# EuroWizard.net
KiCad netlist of a schematic drawn in EAGLE
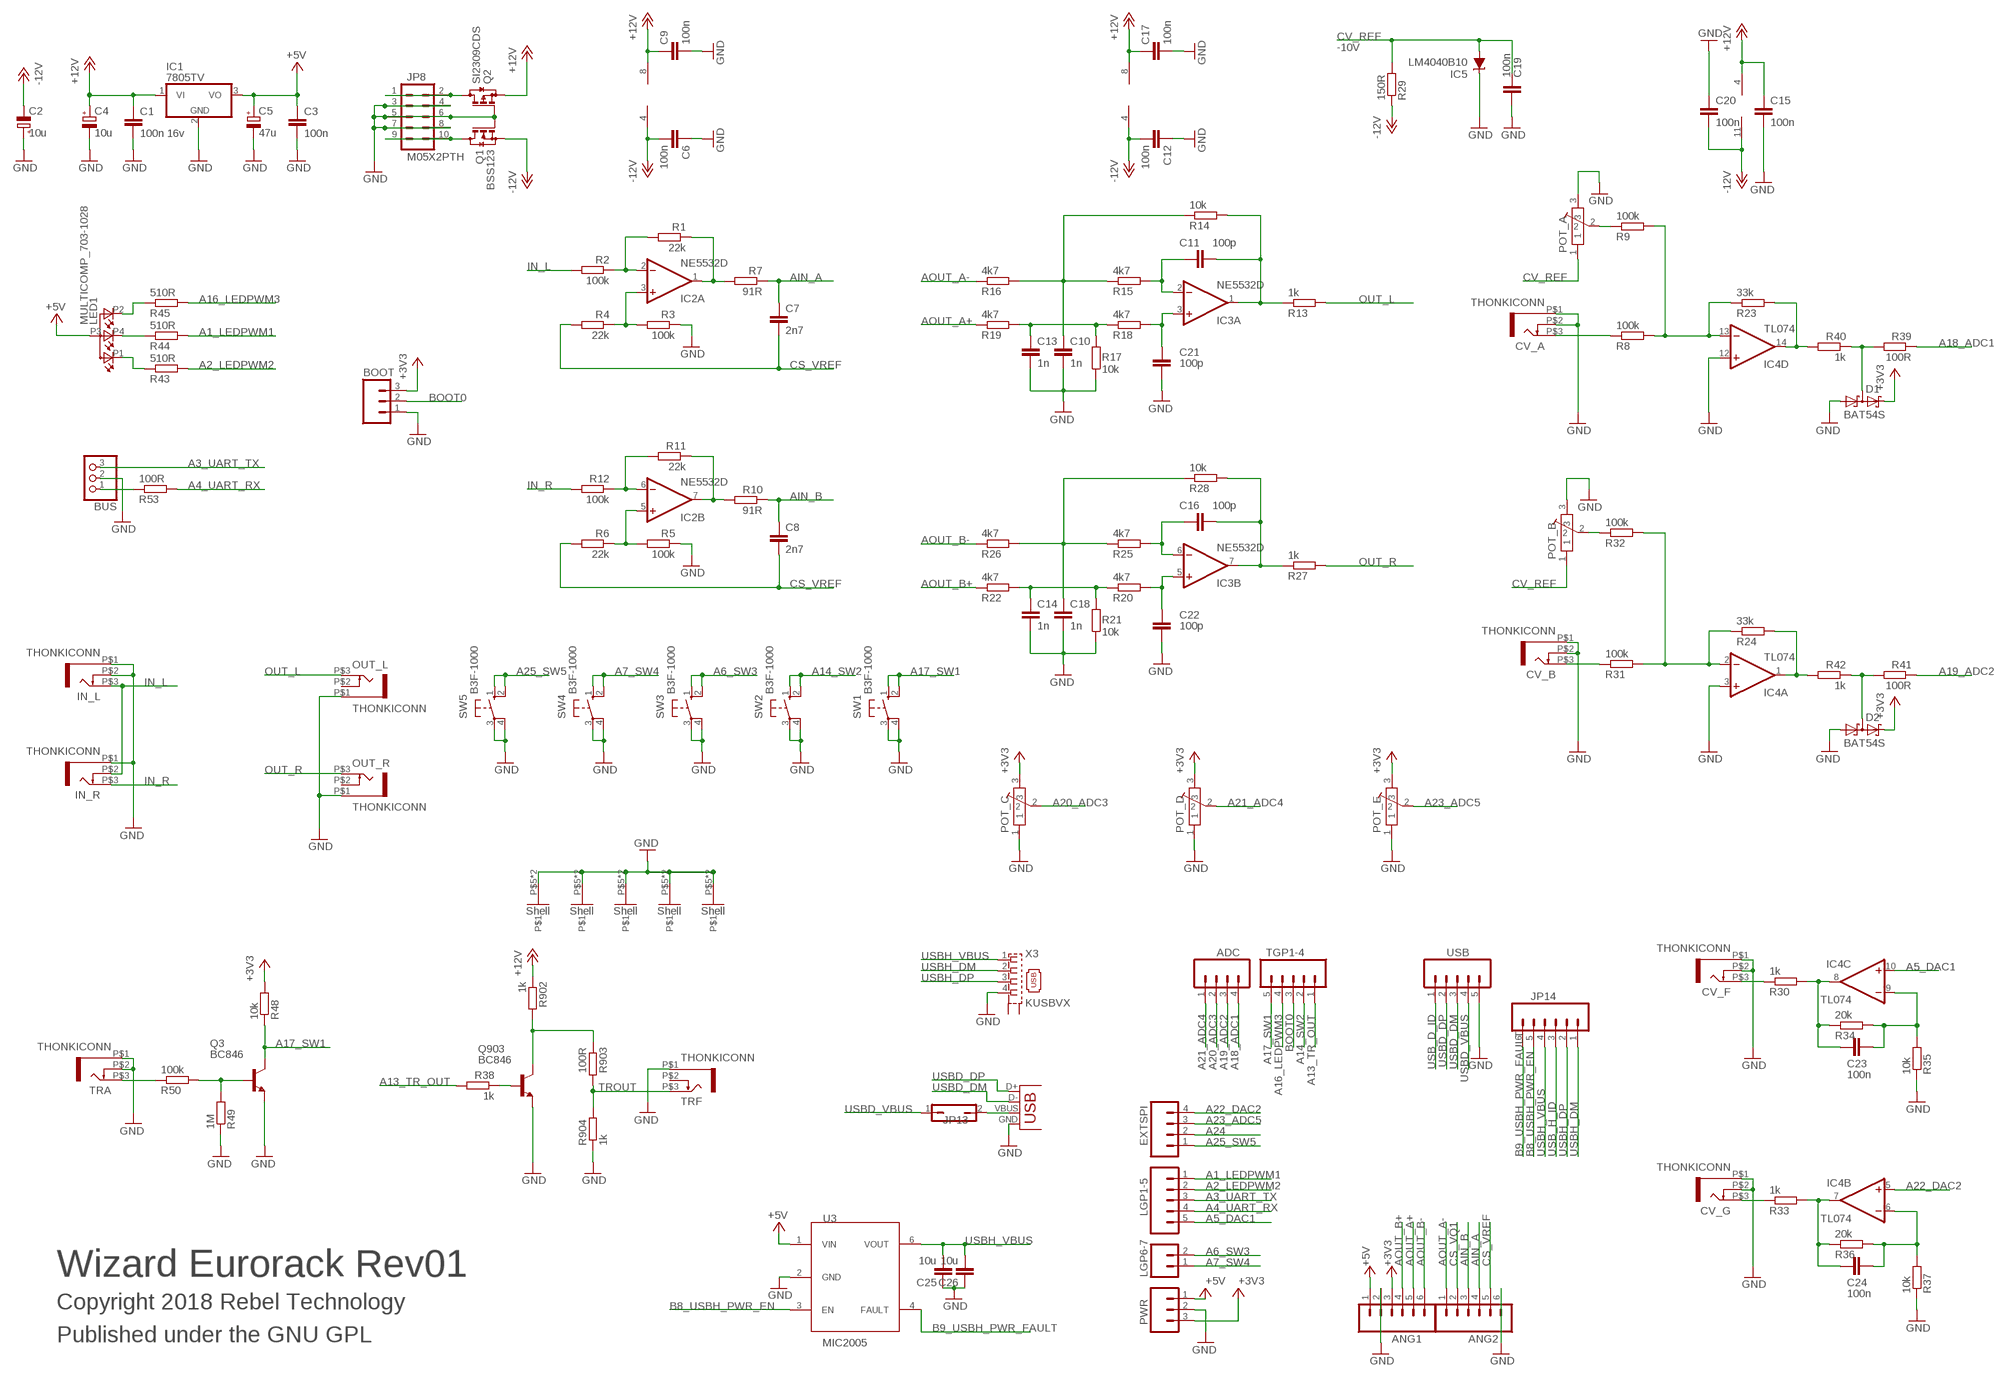
[diagram p0: schematic, sheet 1]

(export (version "E")
  (design (tool "Eeschema 10.0.6"))
  (components
    (comp (ref "ADC")
      (value "M04PTH")
      (footprint "eagle-import:1X04")
      (libsource (lib "eagle-import") (part "M04PTH"))
    )
    (comp (ref "ANG1")
      (value "M06SIP")
      (footprint "eagle-import:1X06")
      (libsource (lib "eagle-import") (part "M06SIP"))
    )
    (comp (ref "ANG2")
      (value "M06SIP")
      (footprint "eagle-import:1X06")
      (libsource (lib "eagle-import") (part "M06SIP"))
    )
    (comp (ref "BOOT")
      (value "M03PTH")
      (footprint "eagle-import:1X03")
      (libsource (lib "eagle-import") (part "M03PTH"))
    )
    (comp (ref "BUS")
      (value "CON-JST-1X03PH-TH")
      (footprint "eagle-import:JST-B3B-PH-KL")
      (libsource (lib "eagle-import") (part "CON-JST-1X03PH-TH"))
    )
    (comp (ref "C1")
      (value "100n 16v")
      (footprint "eagle-import:C0603")
      (libsource (lib "eagle-import") (part "C-EUC0603"))
    )
    (comp (ref "C2")
      (value "10u")
      (footprint "eagle-import:UD-4X5,8_NICHICON")
      (libsource (lib "eagle-import") (part "CPOL-EUUD-4X5,8"))
    )
    (comp (ref "C3")
      (value "100n")
      (footprint "eagle-import:C0603")
      (libsource (lib "eagle-import") (part "C-EUC0603"))
    )
    (comp (ref "C4")
      (value "10u")
      (footprint "eagle-import:UD-4X5,8_NICHICON")
      (libsource (lib "eagle-import") (part "CPOL-EUUD-4X5,8"))
    )
    (comp (ref "C5")
      (value "47u")
      (footprint "eagle-import:UD-4X5,8_NICHICON")
      (libsource (lib "eagle-import") (part "rcl_CPOL-EUUD-4X5,8"))
    )
    (comp (ref "C6")
      (value "100n")
      (footprint "eagle-import:C0603")
      (libsource (lib "eagle-import") (part "resistor_C-EUC0603"))
    )
    (comp (ref "C7")
      (value "2n7")
      (footprint "eagle-import:C0603")
      (libsource (lib "eagle-import") (part "resistor_C-EUC0603"))
    )
    (comp (ref "C8")
      (value "2n7")
      (footprint "eagle-import:C0603")
      (libsource (lib "eagle-import") (part "resistor_C-EUC0603"))
    )
    (comp (ref "C9")
      (value "100n")
      (footprint "eagle-import:C0603")
      (libsource (lib "eagle-import") (part "resistor_C-EUC0603"))
    )
    (comp (ref "C10")
      (value "1n")
      (footprint "eagle-import:C0603")
      (libsource (lib "eagle-import") (part "resistor_C-EUC0603"))
    )
    (comp (ref "C11")
      (value "100p")
      (footprint "eagle-import:C0603")
      (libsource (lib "eagle-import") (part "resistor_C-EUC0603"))
    )
    (comp (ref "C12")
      (value "100n")
      (footprint "eagle-import:C0603")
      (libsource (lib "eagle-import") (part "resistor_C-EUC0603"))
    )
    (comp (ref "C13")
      (value "1n")
      (footprint "eagle-import:C0603")
      (libsource (lib "eagle-import") (part "resistor_C-EUC0603"))
    )
    (comp (ref "C14")
      (value "1n")
      (footprint "eagle-import:C0603")
      (libsource (lib "eagle-import") (part "resistor_C-EUC0603"))
    )
    (comp (ref "C15")
      (value "100n")
      (footprint "eagle-import:C0603")
      (libsource (lib "eagle-import") (part "resistor_C-EUC0603"))
    )
    (comp (ref "C16")
      (value "100p")
      (footprint "eagle-import:C0603")
      (libsource (lib "eagle-import") (part "resistor_C-EUC0603"))
    )
    (comp (ref "C17")
      (value "100n")
      (footprint "eagle-import:C0603")
      (libsource (lib "eagle-import") (part "resistor_C-EUC0603"))
    )
    (comp (ref "C18")
      (value "1n")
      (footprint "eagle-import:C0603")
      (libsource (lib "eagle-import") (part "resistor_C-EUC0603"))
    )
    (comp (ref "C19")
      (value "100n")
      (footprint "eagle-import:C0603")
      (libsource (lib "eagle-import") (part "resistor_C-EUC0603"))
    )
    (comp (ref "C20")
      (value "100n")
      (footprint "eagle-import:C0603")
      (libsource (lib "eagle-import") (part "resistor_C-EUC0603"))
    )
    (comp (ref "C21")
      (value "100p")
      (footprint "eagle-import:C0603")
      (libsource (lib "eagle-import") (part "resistor_C-EUC0603"))
    )
    (comp (ref "C22")
      (value "100p")
      (footprint "eagle-import:C0603")
      (libsource (lib "eagle-import") (part "resistor_C-EUC0603"))
    )
    (comp (ref "C23")
      (value "100n")
      (footprint "eagle-import:C0603")
      (libsource (lib "eagle-import") (part "C-EUC0603"))
    )
    (comp (ref "C24")
      (value "100n")
      (footprint "eagle-import:C0603")
      (libsource (lib "eagle-import") (part "C-EUC0603"))
    )
    (comp (ref "C25")
      (value "10u")
      (footprint "eagle-import:C0603")
      (libsource (lib "eagle-import") (part "resistor_C-EUC0603"))
    )
    (comp (ref "C26")
      (value "10u")
      (footprint "eagle-import:C0603")
      (libsource (lib "eagle-import") (part "resistor_C-EUC0603"))
    )
    (comp (ref "CV_A")
      (value "THONKICONN")
      (footprint "eagle-import:THONKICONN")
      (libsource (lib "eagle-import") (part "THONKICONN"))
    )
    (comp (ref "CV_B")
      (value "THONKICONN")
      (footprint "eagle-import:THONKICONN")
      (libsource (lib "eagle-import") (part "THONKICONN"))
    )
    (comp (ref "CV_F")
      (value "THONKICONN")
      (footprint "eagle-import:THONKICONN")
      (libsource (lib "eagle-import") (part "THONKICONN"))
    )
    (comp (ref "CV_G")
      (value "THONKICONN")
      (footprint "eagle-import:THONKICONN")
      (libsource (lib "eagle-import") (part "THONKICONN"))
    )
    (comp (ref "D1")
      (value "BAT54S")
      (footprint "eagle-import:SOT23")
      (libsource (lib "eagle-import") (part "BAT54S"))
    )
    (comp (ref "D2")
      (value "BAT54S")
      (footprint "eagle-import:SOT23")
      (libsource (lib "eagle-import") (part "BAT54S"))
    )
    (comp (ref "EXTSPI")
      (value "M04PTH")
      (footprint "eagle-import:1X04")
      (libsource (lib "eagle-import") (part "M04PTH"))
    )
    (comp (ref "IC1")
      (value "7805TV")
      (footprint "eagle-import:TO220V")
      (libsource (lib "eagle-import") (part "78TV05"))
    )
    (comp (ref "IC2")
      (value "NE5532D")
      (footprint "eagle-import:SO08")
      (libsource (lib "eagle-import") (part "NE5532D"))
    )
    (comp (ref "IC3")
      (value "NE5532D")
      (footprint "eagle-import:SO08")
      (libsource (lib "eagle-import") (part "NE5532D"))
    )
    (comp (ref "IC4")
      (value "TL074")
      (footprint "eagle-import:SO14")
      (libsource (lib "eagle-import") (part "QUAD_OPAMPD"))
    )
    (comp (ref "IC5")
      (value "LM4040B10")
      (footprint "eagle-import:DBZ_R-PDSO-G3")
      (fields (field (name "MF") "TEXAS INSTRUMENT CONNECTORS") (field (name "MPN") "LM4041C12QDBZT"))
      (libsource (lib "eagle-import") (part "LM4041DBZC12"))
    )
    (comp (ref "IN_L")
      (value "THONKICONN")
      (footprint "eagle-import:THONKICONN")
      (libsource (lib "eagle-import") (part "THONKICONN"))
    )
    (comp (ref "IN_R")
      (value "THONKICONN")
      (footprint "eagle-import:THONKICONN")
      (libsource (lib "eagle-import") (part "THONKICONN"))
    )
    (comp (ref "JP8")
      (value "M05X2PTH")
      (footprint "eagle-import:AVR_ICSP")
      (libsource (lib "eagle-import") (part "M05X2PTH"))
    )
    (comp (ref "JP13")
      (value "JP1Q")
      (footprint "eagle-import:JP1")
      (libsource (lib "eagle-import") (part "JP1Q"))
    )
    (comp (ref "JP14")
      (value "M06SIP")
      (footprint "eagle-import:1X06")
      (libsource (lib "eagle-import") (part "M06SIP"))
    )
    (comp (ref "LED1")
      (value "MULTICOMP_703-1028")
      (footprint "eagle-import:RGB-LED-703-1028")
      (libsource (lib "eagle-import") (part "MULTICOMP_703-1028"))
    )
    (comp (ref "LGP1-5")
      (value "M05PTH")
      (footprint "eagle-import:1X05")
      (libsource (lib "eagle-import") (part "M05PTH"))
    )
    (comp (ref "LGP6-7")
      (value "M02PTH")
      (footprint "eagle-import:1X02")
      (libsource (lib "eagle-import") (part "M02PTH"))
    )
    (comp (ref "OUT_L")
      (value "THONKICONN")
      (footprint "eagle-import:THONKICONN")
      (libsource (lib "eagle-import") (part "THONKICONN"))
    )
    (comp (ref "OUT_R")
      (value "THONKICONN")
      (footprint "eagle-import:THONKICONN")
      (libsource (lib "eagle-import") (part "THONKICONN"))
    )
    (comp (ref "POT_A")
      (value "POT-ALPS-RK09L1140")
      (footprint "eagle-import:POT-ALPS-RK09L1140")
      (libsource (lib "eagle-import") (part "POT-ALPS-RK09L1140"))
    )
    (comp (ref "POT_B")
      (value "POT-ALPS-RK09L1140")
      (footprint "eagle-import:POT-ALPS-RK09L1140")
      (libsource (lib "eagle-import") (part "POT-ALPS-RK09L1140"))
    )
    (comp (ref "POT_C")
      (value "POT-ALPS-RK09L1140")
      (footprint "eagle-import:POT-ALPS-RK09L1140")
      (libsource (lib "eagle-import") (part "POT-ALPS-RK09L1140"))
    )
    (comp (ref "POT_D")
      (value "POT-ALPS-RK09L1140")
      (footprint "eagle-import:POT-ALPS-RK09L1140")
      (libsource (lib "eagle-import") (part "POT-ALPS-RK09L1140"))
    )
    (comp (ref "POT_E")
      (value "POT-ALPS-RK09L1140")
      (footprint "eagle-import:POT-ALPS-RK09L1140")
      (libsource (lib "eagle-import") (part "POT-ALPS-RK09L1140"))
    )
    (comp (ref "PWR")
      (value "M03PTH")
      (footprint "eagle-import:1X03")
      (libsource (lib "eagle-import") (part "M03PTH"))
    )
    (comp (ref "Q1")
      (value "BSS123")
      (footprint "eagle-import:SOT23")
      (libsource (lib "eagle-import") (part "BSS123"))
    )
    (comp (ref "Q2")
      (value "SI2309CDS")
      (footprint "eagle-import:SOT23")
      (libsource (lib "eagle-import") (part "BSS84"))
    )
    (comp (ref "Q3")
      (value "BC846")
      (footprint "eagle-import:SOT23")
      (libsource (lib "eagle-import") (part "BC846"))
    )
    (comp (ref "Q903")
      (value "BC846")
      (footprint "eagle-import:SOT23")
      (libsource (lib "eagle-import") (part "BC846"))
    )
    (comp (ref "R1")
      (value "22k")
      (footprint "eagle-import:0603")
      (libsource (lib "eagle-import") (part "R-EU_0603"))
    )
    (comp (ref "R2")
      (value "100k")
      (footprint "eagle-import:0603")
      (libsource (lib "eagle-import") (part "R-EU_0603"))
    )
    (comp (ref "R3")
      (value "100k")
      (footprint "eagle-import:0603")
      (libsource (lib "eagle-import") (part "R-EU_0603"))
    )
    (comp (ref "R4")
      (value "22k")
      (footprint "eagle-import:0603")
      (libsource (lib "eagle-import") (part "R-EU_0603"))
    )
    (comp (ref "R5")
      (value "100k")
      (footprint "eagle-import:0603")
      (libsource (lib "eagle-import") (part "R-EU_0603"))
    )
    (comp (ref "R6")
      (value "22k")
      (footprint "eagle-import:0603")
      (libsource (lib "eagle-import") (part "R-EU_0603"))
    )
    (comp (ref "R7")
      (value "91R")
      (footprint "eagle-import:0603")
      (libsource (lib "eagle-import") (part "R-EU_0603"))
    )
    (comp (ref "R8")
      (value "100k")
      (footprint "eagle-import:0603")
      (libsource (lib "eagle-import") (part "R-EU_0603"))
    )
    (comp (ref "R9")
      (value "100k")
      (footprint "eagle-import:0603")
      (libsource (lib "eagle-import") (part "R-EU_0603"))
    )
    (comp (ref "R10")
      (value "91R")
      (footprint "eagle-import:0603")
      (libsource (lib "eagle-import") (part "R-EU_0603"))
    )
    (comp (ref "R11")
      (value "22k")
      (footprint "eagle-import:0603")
      (libsource (lib "eagle-import") (part "R-EU_0603"))
    )
    (comp (ref "R12")
      (value "100k")
      (footprint "eagle-import:0603")
      (libsource (lib "eagle-import") (part "R-EU_0603"))
    )
    (comp (ref "R13")
      (value "1k")
      (footprint "eagle-import:0603")
      (libsource (lib "eagle-import") (part "R-EU_0603"))
    )
    (comp (ref "R14")
      (value "10k")
      (footprint "eagle-import:0603")
      (libsource (lib "eagle-import") (part "R-EU_0603"))
    )
    (comp (ref "R15")
      (value "4k7")
      (footprint "eagle-import:0603")
      (libsource (lib "eagle-import") (part "R-EU_0603"))
    )
    (comp (ref "R16")
      (value "4k7")
      (footprint "eagle-import:0603")
      (libsource (lib "eagle-import") (part "R-EU_0603"))
    )
    (comp (ref "R17")
      (value "10k")
      (footprint "eagle-import:0603")
      (libsource (lib "eagle-import") (part "R-EU_0603"))
    )
    (comp (ref "R18")
      (value "4k7")
      (footprint "eagle-import:0603")
      (libsource (lib "eagle-import") (part "R-EU_0603"))
    )
    (comp (ref "R19")
      (value "4k7")
      (footprint "eagle-import:0603")
      (libsource (lib "eagle-import") (part "R-EU_0603"))
    )
    (comp (ref "R20")
      (value "4k7")
      (footprint "eagle-import:0603")
      (libsource (lib "eagle-import") (part "R-EU_0603"))
    )
    (comp (ref "R21")
      (value "10k")
      (footprint "eagle-import:0603")
      (libsource (lib "eagle-import") (part "R-EU_0603"))
    )
    (comp (ref "R22")
      (value "4k7")
      (footprint "eagle-import:0603")
      (libsource (lib "eagle-import") (part "R-EU_0603"))
    )
    (comp (ref "R23")
      (value "33k")
      (footprint "eagle-import:0603")
      (libsource (lib "eagle-import") (part "R-EU_0603"))
    )
    (comp (ref "R24")
      (value "33k")
      (footprint "eagle-import:0603")
      (libsource (lib "eagle-import") (part "R-EU_0603"))
    )
    (comp (ref "R25")
      (value "4k7")
      (footprint "eagle-import:0603")
      (libsource (lib "eagle-import") (part "R-EU_0603"))
    )
    (comp (ref "R26")
      (value "4k7")
      (footprint "eagle-import:0603")
      (libsource (lib "eagle-import") (part "R-EU_0603"))
    )
    (comp (ref "R27")
      (value "1k")
      (footprint "eagle-import:0603")
      (libsource (lib "eagle-import") (part "R-EU_0603"))
    )
    (comp (ref "R28")
      (value "10k")
      (footprint "eagle-import:0603")
      (libsource (lib "eagle-import") (part "R-EU_0603"))
    )
    (comp (ref "R29")
      (value "150R")
      (footprint "eagle-import:0603")
      (libsource (lib "eagle-import") (part "R-EU_0603"))
    )
    (comp (ref "R30")
      (value "1k")
      (footprint "eagle-import:0603")
      (libsource (lib "eagle-import") (part "R-EU_0603"))
    )
    (comp (ref "R31")
      (value "100k")
      (footprint "eagle-import:0603")
      (libsource (lib "eagle-import") (part "R-EU_0603"))
    )
    (comp (ref "R32")
      (value "100k")
      (footprint "eagle-import:0603")
      (libsource (lib "eagle-import") (part "R-EU_0603"))
    )
    (comp (ref "R33")
      (value "1k")
      (footprint "eagle-import:0603")
      (libsource (lib "eagle-import") (part "R-EU_0603"))
    )
    (comp (ref "R34")
      (value "20k")
      (footprint "eagle-import:0603")
      (libsource (lib "eagle-import") (part "R-EU_0603"))
    )
    (comp (ref "R35")
      (value "10k")
      (footprint "eagle-import:0603")
      (libsource (lib "eagle-import") (part "R-EU_0603"))
    )
    (comp (ref "R36")
      (value "20k")
      (footprint "eagle-import:0603")
      (libsource (lib "eagle-import") (part "R-EU_0603"))
    )
    (comp (ref "R37")
      (value "10k")
      (footprint "eagle-import:0603")
      (libsource (lib "eagle-import") (part "R-EU_0603"))
    )
    (comp (ref "R38")
      (value "1k")
      (footprint "eagle-import:0603")
      (libsource (lib "eagle-import") (part "R-EU_0603"))
    )
    (comp (ref "R39")
      (value "100R")
      (footprint "eagle-import:0603")
      (libsource (lib "eagle-import") (part "R-EU_0603"))
    )
    (comp (ref "R40")
      (value "1k")
      (footprint "eagle-import:0603")
      (libsource (lib "eagle-import") (part "R-EU_0603"))
    )
    (comp (ref "R41")
      (value "100R")
      (footprint "eagle-import:0603")
      (libsource (lib "eagle-import") (part "R-EU_0603"))
    )
    (comp (ref "R42")
      (value "1k")
      (footprint "eagle-import:0603")
      (libsource (lib "eagle-import") (part "R-EU_0603"))
    )
    (comp (ref "R43")
      (value "510R")
      (footprint "eagle-import:0603")
      (libsource (lib "eagle-import") (part "R-EU_0603"))
    )
    (comp (ref "R44")
      (value "510R")
      (footprint "eagle-import:0603")
      (libsource (lib "eagle-import") (part "R-EU_0603"))
    )
    (comp (ref "R45")
      (value "510R")
      (footprint "eagle-import:0603")
      (libsource (lib "eagle-import") (part "R-EU_0603"))
    )
    (comp (ref "R48")
      (value "10k")
      (footprint "eagle-import:0603")
      (libsource (lib "eagle-import") (part "R-EU_0603"))
    )
    (comp (ref "R49")
      (value "1M")
      (footprint "eagle-import:0603")
      (libsource (lib "eagle-import") (part "R-EU_0603"))
    )
    (comp (ref "R50")
      (value "100k")
      (footprint "eagle-import:0603")
      (libsource (lib "eagle-import") (part "R-EU_0603"))
    )
    (comp (ref "R53")
      (value "100R")
      (footprint "eagle-import:0603")
      (libsource (lib "eagle-import") (part "R-EU_0603"))
    )
    (comp (ref "R902")
      (value "1k")
      (footprint "eagle-import:0603")
      (libsource (lib "eagle-import") (part "R-EU_0603"))
    )
    (comp (ref "R903")
      (value "100R")
      (footprint "eagle-import:0603")
      (libsource (lib "eagle-import") (part "R-EU_0603"))
    )
    (comp (ref "R904")
      (value "1k")
      (footprint "eagle-import:0603")
      (libsource (lib "eagle-import") (part "R-EU_0603"))
    )
    (comp (ref "SW1")
      (value "B3F-1000")
      (footprint "eagle-import:B3F-10XX")
      (libsource (lib "eagle-import") (part "10-XX"))
    )
    (comp (ref "SW2")
      (value "B3F-1000")
      (footprint "eagle-import:B3F-10XX")
      (libsource (lib "eagle-import") (part "10-XX"))
    )
    (comp (ref "SW3")
      (value "B3F-1000")
      (footprint "eagle-import:B3F-10XX")
      (libsource (lib "eagle-import") (part "10-XX"))
    )
    (comp (ref "SW4")
      (value "B3F-1000")
      (footprint "eagle-import:B3F-10XX")
      (libsource (lib "eagle-import") (part "10-XX"))
    )
    (comp (ref "SW5")
      (value "B3F-1000")
      (footprint "eagle-import:B3F-10XX")
      (libsource (lib "eagle-import") (part "10-XX"))
    )
    (comp (ref "TGP1-4")
      (value "M05PTH")
      (footprint "eagle-import:1X05")
      (libsource (lib "eagle-import") (part "M05PTH"))
    )
    (comp (ref "TRA")
      (value "THONKICONN")
      (footprint "eagle-import:THONKICONN")
      (libsource (lib "eagle-import") (part "THONKICONN"))
    )
    (comp (ref "TRF")
      (value "THONKICONN")
      (footprint "eagle-import:THONKICONN")
      (libsource (lib "eagle-import") (part "THONKICONN"))
    )
    (comp (ref "U3")
      (value "MIC2005")
      (footprint "eagle-import:SOT23-6")
      (libsource (lib "eagle-import") (part "MIC2005"))
    )
    (comp (ref "USB")
      (value "M05PTH")
      (footprint "eagle-import:1X05")
      (libsource (lib "eagle-import") (part "M05PTH"))
    )
    (comp (ref "X3")
      (value "KUSBVX")
      (footprint "eagle-import:KUSBVX")
      (libsource (lib "eagle-import") (part "KUSBVX"))
    )
    (comp (ref "X5")
      (value "USBPTH-VERTICAL")
      (footprint "eagle-import:USB-B-PTH-VERTICAL")
      (libsource (lib "eagle-import") (part "USBPTH-VERTICAL"))
    )
  )
  (nets
    (net (code "1") (name "+3V3") (class "Default")
      (node (ref "ANG1") (pin "3") (pinfunction "3_3") (pintype "passive"))
      (node (ref "BOOT") (pin "3") (pinfunction "3_3") (pintype "passive"))
      (node (ref "D1") (pin "2") (pinfunction "C2_2") (pintype "passive"))
      (node (ref "D2") (pin "2") (pinfunction "C2_2") (pintype "passive"))
      (node (ref "POT_C") (pin "3") (pinfunction "3_3") (pintype "bidirectional"))
      (node (ref "POT_D") (pin "3") (pinfunction "3_3") (pintype "bidirectional"))
      (node (ref "POT_E") (pin "3") (pinfunction "3_3") (pintype "bidirectional"))
      (node (ref "PWR") (pin "3") (pinfunction "3_3") (pintype "passive"))
      (node (ref "R48") (pin "2") (pinfunction "2_2") (pintype "passive"))
    )
    (net (code "2") (name "+5V") (class "Default")
      (node (ref "ANG1") (pin "1") (pinfunction "1_1") (pintype "passive"))
      (node (ref "C3") (pin "1") (pinfunction "1_1") (pintype "passive"))
      (node (ref "C5") (pin "+") (pinfunction "+_+") (pintype "passive"))
      (node (ref "IC1") (pin "3") (pinfunction "VO_3") (pintype "passive"))
      (node (ref "LED1") (pin "P3") (pinfunction "A_P3") (pintype "passive"))
      (node (ref "PWR") (pin "1") (pinfunction "1_1") (pintype "passive"))
      (node (ref "U3") (pin "1") (pinfunction "VIN_1") (pintype "power_in"))
    )
    (net (code "3") (name "+12V") (class "Default")
      (node (ref "C1") (pin "1") (pinfunction "1_1") (pintype "passive"))
      (node (ref "C15") (pin "1") (pinfunction "1_1") (pintype "passive"))
      (node (ref "C17") (pin "1") (pinfunction "1_1") (pintype "passive"))
      (node (ref "C4") (pin "+") (pinfunction "+_+") (pintype "passive"))
      (node (ref "C9") (pin "1") (pinfunction "1_1") (pintype "passive"))
      (node (ref "IC1") (pin "1") (pinfunction "VI_1") (pintype "input"))
      (node (ref "IC2") (pin "8") (pinfunction "V+_8") (pintype "power_in"))
      (node (ref "IC3") (pin "8") (pinfunction "V+_8") (pintype "power_in"))
      (node (ref "IC4") (pin "4") (pinfunction "V+_4") (pintype "power_in"))
      (node (ref "Q2") (pin "2") (pinfunction "S_2") (pintype "passive"))
      (node (ref "R902") (pin "1") (pinfunction "1_1") (pintype "passive"))
    )
    (net (code "4") (name "-12V") (class "Default")
      (node (ref "C12") (pin "2") (pinfunction "2_2") (pintype "passive"))
      (node (ref "C2") (pin "-") (pinfunction "-_-") (pintype "passive"))
      (node (ref "C20") (pin "2") (pinfunction "2_2") (pintype "passive"))
      (node (ref "C6") (pin "2") (pinfunction "2_2") (pintype "passive"))
      (node (ref "IC2") (pin "4") (pinfunction "V-_4") (pintype "power_in"))
      (node (ref "IC3") (pin "4") (pinfunction "V-_4") (pintype "power_in"))
      (node (ref "IC4") (pin "11") (pinfunction "V-_11") (pintype "power_in"))
      (node (ref "Q1") (pin "2") (pinfunction "S_2") (pintype "passive"))
      (node (ref "R29") (pin "1") (pinfunction "1_1") (pintype "passive"))
    )
    (net (code "5") (name "/A1_LEDPWM1") (class "Default")
      (node (ref "LGP1-5") (pin "1") (pinfunction "1_1") (pintype "passive"))
      (node (ref "R44") (pin "2") (pinfunction "2_2") (pintype "passive"))
    )
    (net (code "6") (name "/A2_LEDPWM2") (class "Default")
      (node (ref "LGP1-5") (pin "2") (pinfunction "2_2") (pintype "passive"))
      (node (ref "R43") (pin "2") (pinfunction "2_2") (pintype "passive"))
    )
    (net (code "7") (name "/A3_UART_TX") (class "Default")
      (node (ref "BUS") (pin "3") (pinfunction "3_3") (pintype "passive"))
      (node (ref "LGP1-5") (pin "3") (pinfunction "3_3") (pintype "passive"))
    )
    (net (code "8") (name "/A4_UART_RX") (class "Default")
      (node (ref "LGP1-5") (pin "4") (pinfunction "4_4") (pintype "passive"))
      (node (ref "R53") (pin "2") (pinfunction "2_2") (pintype "passive"))
    )
    (net (code "9") (name "/A5_DAC1") (class "Default")
      (node (ref "IC4") (pin "10") (pinfunction "+IN_10") (pintype "input"))
      (node (ref "LGP1-5") (pin "5") (pinfunction "5_5") (pintype "passive"))
    )
    (net (code "10") (name "/A6_SW3") (class "Default")
      (node (ref "LGP6-7") (pin "2") (pinfunction "2_2") (pintype "passive"))
      (node (ref "SW3") (pin "1") (pinfunction "S_1") (pintype "passive"))
      (node (ref "SW3") (pin "2") (pinfunction "S1_2") (pintype "passive"))
    )
    (net (code "11") (name "/A7_SW4") (class "Default")
      (node (ref "LGP6-7") (pin "1") (pinfunction "1_1") (pintype "passive"))
      (node (ref "SW4") (pin "1") (pinfunction "S_1") (pintype "passive"))
      (node (ref "SW4") (pin "2") (pinfunction "S1_2") (pintype "passive"))
    )
    (net (code "12") (name "/A13_TR_OUT") (class "Default")
      (node (ref "R38") (pin "2") (pinfunction "2_2") (pintype "passive"))
      (node (ref "TGP1-4") (pin "1") (pinfunction "1_1") (pintype "passive"))
    )
    (net (code "13") (name "/A14_SW2") (class "Default")
      (node (ref "SW2") (pin "1") (pinfunction "S_1") (pintype "passive"))
      (node (ref "SW2") (pin "2") (pinfunction "S1_2") (pintype "passive"))
      (node (ref "TGP1-4") (pin "2") (pinfunction "2_2") (pintype "passive"))
    )
    (net (code "14") (name "/A16_LEDPWM3") (class "Default")
      (node (ref "R45") (pin "2") (pinfunction "2_2") (pintype "passive"))
      (node (ref "TGP1-4") (pin "4") (pinfunction "4_4") (pintype "passive"))
    )
    (net (code "15") (name "/A17_SW1") (class "Default")
      (node (ref "Q3") (pin "3") (pinfunction "C_3") (pintype "passive"))
      (node (ref "R48") (pin "1") (pinfunction "1_1") (pintype "passive"))
      (node (ref "SW1") (pin "1") (pinfunction "S_1") (pintype "passive"))
      (node (ref "SW1") (pin "2") (pinfunction "S1_2") (pintype "passive"))
      (node (ref "TGP1-4") (pin "5") (pinfunction "5_5") (pintype "passive"))
    )
    (net (code "16") (name "/A18_ADC1") (class "Default")
      (node (ref "ADC") (pin "4") (pinfunction "4_4") (pintype "passive"))
      (node (ref "R39") (pin "1") (pinfunction "1_1") (pintype "passive"))
    )
    (net (code "17") (name "/A19_ADC2") (class "Default")
      (node (ref "ADC") (pin "3") (pinfunction "3_3") (pintype "passive"))
      (node (ref "R41") (pin "1") (pinfunction "1_1") (pintype "passive"))
    )
    (net (code "18") (name "/A20_ADC3") (class "Default")
      (node (ref "ADC") (pin "2") (pinfunction "2_2") (pintype "passive"))
      (node (ref "POT_C") (pin "2") (pinfunction "2_2") (pintype "bidirectional"))
    )
    (net (code "19") (name "/A21_ADC4") (class "Default")
      (node (ref "ADC") (pin "1") (pinfunction "1_1") (pintype "passive"))
      (node (ref "POT_D") (pin "2") (pinfunction "2_2") (pintype "bidirectional"))
    )
    (net (code "20") (name "/A22_DAC2") (class "Default")
      (node (ref "EXTSPI") (pin "4") (pinfunction "4_4") (pintype "passive"))
      (node (ref "IC4") (pin "5") (pinfunction "+IN_5") (pintype "input"))
    )
    (net (code "21") (name "/A23_ADC5") (class "Default")
      (node (ref "EXTSPI") (pin "3") (pinfunction "3_3") (pintype "passive"))
      (node (ref "POT_E") (pin "2") (pinfunction "2_2") (pintype "bidirectional"))
    )
    (net (code "22") (name "/A24") (class "Default")
      (node (ref "EXTSPI") (pin "2") (pinfunction "2_2") (pintype "passive"))
    )
    (net (code "23") (name "/A25_SW5") (class "Default")
      (node (ref "EXTSPI") (pin "1") (pinfunction "1_1") (pintype "passive"))
      (node (ref "SW5") (pin "1") (pinfunction "S_1") (pintype "passive"))
      (node (ref "SW5") (pin "2") (pinfunction "S1_2") (pintype "passive"))
    )
    (net (code "24") (name "/AIN_A") (class "Default")
      (node (ref "ANG2") (pin "4") (pinfunction "4_4") (pintype "passive"))
      (node (ref "C7") (pin "1") (pinfunction "1_1") (pintype "passive"))
      (node (ref "R7") (pin "1") (pinfunction "1_1") (pintype "passive"))
    )
    (net (code "25") (name "/AIN_B") (class "Default")
      (node (ref "ANG2") (pin "3") (pinfunction "3_3") (pintype "passive"))
      (node (ref "C8") (pin "1") (pinfunction "1_1") (pintype "passive"))
      (node (ref "R10") (pin "1") (pinfunction "1_1") (pintype "passive"))
    )
    (net (code "26") (name "/AOUT_A+") (class "Default")
      (node (ref "ANG1") (pin "5") (pinfunction "5_5") (pintype "passive"))
      (node (ref "R19") (pin "1") (pinfunction "1_1") (pintype "passive"))
    )
    (net (code "27") (name "/AOUT_A-") (class "Default")
      (node (ref "ANG2") (pin "1") (pinfunction "1_1") (pintype "passive"))
      (node (ref "R16") (pin "1") (pinfunction "1_1") (pintype "passive"))
    )
    (net (code "28") (name "/AOUT_B+") (class "Default")
      (node (ref "ANG1") (pin "4") (pinfunction "4_4") (pintype "passive"))
      (node (ref "R22") (pin "1") (pinfunction "1_1") (pintype "passive"))
    )
    (net (code "29") (name "/AOUT_B-") (class "Default")
      (node (ref "ANG1") (pin "6") (pinfunction "6_6") (pintype "passive"))
      (node (ref "R26") (pin "1") (pinfunction "1_1") (pintype "passive"))
    )
    (net (code "30") (name "/B8_USBH_PWR_EN") (class "Default")
      (node (ref "JP14") (pin "5") (pinfunction "5_5") (pintype "passive"))
      (node (ref "U3") (pin "3") (pinfunction "EN_3") (pintype "input"))
    )
    (net (code "31") (name "/B9_USBH_PWR_FAULT") (class "Default")
      (node (ref "JP14") (pin "6") (pinfunction "6_6") (pintype "passive"))
      (node (ref "U3") (pin "4") (pinfunction "FAULT_4") (pintype "output"))
    )
    (net (code "32") (name "/BOOT0") (class "Default")
      (node (ref "BOOT") (pin "2") (pinfunction "2_2") (pintype "passive"))
      (node (ref "TGP1-4") (pin "3") (pinfunction "3_3") (pintype "passive"))
    )
    (net (code "33") (name "/CS_VQ1") (class "Default")
      (node (ref "ANG2") (pin "2") (pinfunction "2_2") (pintype "passive"))
    )
    (net (code "34") (name "/CS_VREF") (class "Default")
      (node (ref "ANG2") (pin "5") (pinfunction "5_5") (pintype "passive"))
      (node (ref "C7") (pin "2") (pinfunction "2_2") (pintype "passive"))
      (node (ref "C8") (pin "2") (pinfunction "2_2") (pintype "passive"))
      (node (ref "R4") (pin "2") (pinfunction "2_2") (pintype "passive"))
      (node (ref "R6") (pin "2") (pinfunction "2_2") (pintype "passive"))
    )
    (net (code "35") (name "/CV_REF") (class "Default")
      (node (ref "C19") (pin "1") (pinfunction "1_1") (pintype "passive"))
      (node (ref "IC5") (pin "2") (pinfunction "A_2") (pintype "passive"))
      (node (ref "POT_A") (pin "1") (pinfunction "1_1") (pintype "bidirectional"))
      (node (ref "POT_B") (pin "1") (pinfunction "1_1") (pintype "bidirectional"))
      (node (ref "R29") (pin "2") (pinfunction "2_2") (pintype "passive"))
    )
    (net (code "36") (name "/IN_L") (class "Default")
      (node (ref "IN_L") (pin "P$3") (pinfunction "3_P$3") (pintype "passive"))
      (node (ref "IN_R") (pin "P$2") (pinfunction "4_P$2") (pintype "passive"))
      (node (ref "R2") (pin "2") (pinfunction "2_2") (pintype "passive"))
    )
    (net (code "37") (name "/IN_R") (class "Default")
      (node (ref "IN_R") (pin "P$3") (pinfunction "3_P$3") (pintype "passive"))
      (node (ref "R12") (pin "2") (pinfunction "2_2") (pintype "passive"))
    )
    (net (code "38") (name "/OUT_L") (class "Default")
      (node (ref "OUT_L") (pin "P$3") (pinfunction "3_P$3") (pintype "passive"))
      (node (ref "R13") (pin "2") (pinfunction "2_2") (pintype "passive"))
    )
    (net (code "39") (name "/OUT_R") (class "Default")
      (node (ref "OUT_R") (pin "P$3") (pinfunction "3_P$3") (pintype "passive"))
      (node (ref "R27") (pin "2") (pinfunction "2_2") (pintype "passive"))
    )
    (net (code "40") (name "/TROUT") (class "Default")
      (node (ref "R903") (pin "2") (pinfunction "2_2") (pintype "passive"))
      (node (ref "R904") (pin "2") (pinfunction "2_2") (pintype "passive"))
      (node (ref "TRF") (pin "P$3") (pinfunction "3_P$3") (pintype "passive"))
    )
    (net (code "41") (name "/USBD_DM") (class "Default")
      (node (ref "USB") (pin "3") (pinfunction "3_3") (pintype "passive"))
      (node (ref "X5") (pin "D-") (pinfunction "D-_D-") (pintype "bidirectional"))
    )
    (net (code "42") (name "/USBD_DP") (class "Default")
      (node (ref "USB") (pin "2") (pinfunction "2_2") (pintype "passive"))
      (node (ref "X5") (pin "D+") (pinfunction "D+_D+") (pintype "bidirectional"))
    )
    (net (code "43") (name "/USBD_VBUS") (class "Default")
      (node (ref "JP13") (pin "1") (pinfunction "1_1") (pintype "passive"))
      (node (ref "USB") (pin "4") (pinfunction "4_4") (pintype "passive"))
    )
    (net (code "44") (name "/USBH_DM") (class "Default")
      (node (ref "JP14") (pin "1") (pinfunction "1_1") (pintype "passive"))
      (node (ref "X3") (pin "2") (pinfunction "2_2") (pintype "passive"))
    )
    (net (code "45") (name "/USBH_DP") (class "Default")
      (node (ref "JP14") (pin "2") (pinfunction "2_2") (pintype "passive"))
      (node (ref "X3") (pin "3") (pinfunction "3_3") (pintype "passive"))
    )
    (net (code "46") (name "/USBH_VBUS") (class "Default")
      (node (ref "C25") (pin "2") (pinfunction "2_2") (pintype "passive"))
      (node (ref "C26") (pin "2") (pinfunction "2_2") (pintype "passive"))
      (node (ref "JP14") (pin "4") (pinfunction "4_4") (pintype "passive"))
      (node (ref "U3") (pin "6") (pinfunction "VOUT_6") (pintype "output"))
      (node (ref "X3") (pin "1") (pinfunction "1_1") (pintype "passive"))
    )
    (net (code "47") (name "/USB_D_ID") (class "Default")
      (node (ref "USB") (pin "1") (pinfunction "1_1") (pintype "passive"))
    )
    (net (code "48") (name "/USB_H_ID") (class "Default")
      (node (ref "JP14") (pin "3") (pinfunction "3_3") (pintype "passive"))
    )
    (net (code "49") (name "GND") (class "Default")
      (node (ref "ANG1") (pin "2") (pinfunction "2_2") (pintype "passive"))
      (node (ref "ANG2") (pin "6") (pinfunction "6_6") (pintype "passive"))
      (node (ref "BOOT") (pin "1") (pinfunction "1_1") (pintype "passive"))
      (node (ref "BUS") (pin "2") (pinfunction "2_2") (pintype "passive"))
      (node (ref "C1") (pin "2") (pinfunction "2_2") (pintype "passive"))
      (node (ref "C10") (pin "2") (pinfunction "2_2") (pintype "passive"))
      (node (ref "C12") (pin "1") (pinfunction "1_1") (pintype "passive"))
      (node (ref "C13") (pin "2") (pinfunction "2_2") (pintype "passive"))
      (node (ref "C14") (pin "2") (pinfunction "2_2") (pintype "passive"))
      (node (ref "C15") (pin "2") (pinfunction "2_2") (pintype "passive"))
      (node (ref "C17") (pin "2") (pinfunction "2_2") (pintype "passive"))
      (node (ref "C18") (pin "2") (pinfunction "2_2") (pintype "passive"))
      (node (ref "C19") (pin "2") (pinfunction "2_2") (pintype "passive"))
      (node (ref "C2") (pin "+") (pinfunction "+_+") (pintype "passive"))
      (node (ref "C20") (pin "1") (pinfunction "1_1") (pintype "passive"))
      (node (ref "C21") (pin "2") (pinfunction "2_2") (pintype "passive"))
      (node (ref "C22") (pin "2") (pinfunction "2_2") (pintype "passive"))
      (node (ref "C25") (pin "1") (pinfunction "1_1") (pintype "passive"))
      (node (ref "C26") (pin "1") (pinfunction "1_1") (pintype "passive"))
      (node (ref "C3") (pin "2") (pinfunction "2_2") (pintype "passive"))
      (node (ref "C4") (pin "-") (pinfunction "-_-") (pintype "passive"))
      (node (ref "C5") (pin "-") (pinfunction "-_-") (pintype "passive"))
      (node (ref "C6") (pin "1") (pinfunction "1_1") (pintype "passive"))
      (node (ref "C9") (pin "2") (pinfunction "2_2") (pintype "passive"))
      (node (ref "CV_A") (pin "P$1") (pinfunction "5_P$1") (pintype "passive"))
      (node (ref "CV_A") (pin "P$2") (pinfunction "4_P$2") (pintype "passive"))
      (node (ref "CV_B") (pin "P$1") (pinfunction "5_P$1") (pintype "passive"))
      (node (ref "CV_B") (pin "P$2") (pinfunction "4_P$2") (pintype "passive"))
      (node (ref "CV_F") (pin "P$1") (pinfunction "5_P$1") (pintype "passive"))
      (node (ref "CV_F") (pin "P$2") (pinfunction "4_P$2") (pintype "passive"))
      (node (ref "CV_G") (pin "P$1") (pinfunction "5_P$1") (pintype "passive"))
      (node (ref "CV_G") (pin "P$2") (pinfunction "4_P$2") (pintype "passive"))
      (node (ref "D1") (pin "1") (pinfunction "A1_1") (pintype "passive"))
      (node (ref "D2") (pin "1") (pinfunction "A1_1") (pintype "passive"))
      (node (ref "IC1") (pin "2") (pinfunction "GND_2") (pintype "passive"))
      (node (ref "IC4") (pin "12") (pinfunction "+IN_12") (pintype "input"))
      (node (ref "IC4") (pin "3") (pinfunction "+IN_3") (pintype "input"))
      (node (ref "IC5") (pin "1") (pinfunction "C_1") (pintype "passive"))
      (node (ref "IN_L") (pin "P$1") (pinfunction "5_P$1") (pintype "passive"))
      (node (ref "IN_L") (pin "P$2") (pinfunction "4_P$2") (pintype "passive"))
      (node (ref "IN_R") (pin "P$1") (pinfunction "5_P$1") (pintype "passive"))
      (node (ref "JP8") (pin "3") (pinfunction "3_3") (pintype "passive"))
      (node (ref "JP8") (pin "4") (pinfunction "4_4") (pintype "passive"))
      (node (ref "JP8") (pin "5") (pinfunction "5_5") (pintype "passive"))
      (node (ref "JP8") (pin "6") (pinfunction "6_6") (pintype "passive"))
      (node (ref "JP8") (pin "7") (pinfunction "7_7") (pintype "passive"))
      (node (ref "JP8") (pin "8") (pinfunction "8_8") (pintype "passive"))
      (node (ref "OUT_L") (pin "P$1") (pinfunction "5_P$1") (pintype "passive"))
      (node (ref "OUT_R") (pin "P$1") (pinfunction "5_P$1") (pintype "passive"))
      (node (ref "POT_A") (pin "3") (pinfunction "3_3") (pintype "bidirectional"))
      (node (ref "POT_A") (pin "P$5") (pinfunction "P$1_P$5") (pintype "bidirectional"))
      (node (ref "POT_A") (pin "P$6") (pinfunction "P$1_P$6") (pintype "bidirectional"))
      (node (ref "POT_B") (pin "3") (pinfunction "3_3") (pintype "bidirectional"))
      (node (ref "POT_B") (pin "P$5") (pinfunction "P$1_P$5") (pintype "bidirectional"))
      (node (ref "POT_B") (pin "P$6") (pinfunction "P$1_P$6") (pintype "bidirectional"))
      (node (ref "POT_C") (pin "1") (pinfunction "1_1") (pintype "bidirectional"))
      (node (ref "POT_C") (pin "P$5") (pinfunction "P$1_P$5") (pintype "bidirectional"))
      (node (ref "POT_C") (pin "P$6") (pinfunction "P$1_P$6") (pintype "bidirectional"))
      (node (ref "POT_D") (pin "1") (pinfunction "1_1") (pintype "bidirectional"))
      (node (ref "POT_D") (pin "P$5") (pinfunction "P$1_P$5") (pintype "bidirectional"))
      (node (ref "POT_D") (pin "P$6") (pinfunction "P$1_P$6") (pintype "bidirectional"))
      (node (ref "POT_E") (pin "1") (pinfunction "1_1") (pintype "bidirectional"))
      (node (ref "POT_E") (pin "P$5") (pinfunction "P$1_P$5") (pintype "bidirectional"))
      (node (ref "POT_E") (pin "P$6") (pinfunction "P$1_P$6") (pintype "bidirectional"))
      (node (ref "PWR") (pin "2") (pinfunction "2_2") (pintype "passive"))
      (node (ref "Q1") (pin "1") (pinfunction "G_1") (pintype "passive"))
      (node (ref "Q2") (pin "1") (pinfunction "G_1") (pintype "passive"))
      (node (ref "Q3") (pin "2") (pinfunction "E_2") (pintype "passive"))
      (node (ref "Q903") (pin "2") (pinfunction "E_2") (pintype "passive"))
      (node (ref "R17") (pin "1") (pinfunction "1_1") (pintype "passive"))
      (node (ref "R21") (pin "1") (pinfunction "1_1") (pintype "passive"))
      (node (ref "R3") (pin "1") (pinfunction "1_1") (pintype "passive"))
      (node (ref "R35") (pin "1") (pinfunction "1_1") (pintype "passive"))
      (node (ref "R37") (pin "1") (pinfunction "1_1") (pintype "passive"))
      (node (ref "R49") (pin "1") (pinfunction "1_1") (pintype "passive"))
      (node (ref "R5") (pin "1") (pinfunction "1_1") (pintype "passive"))
      (node (ref "R904") (pin "1") (pinfunction "1_1") (pintype "passive"))
      (node (ref "SW1") (pin "3") (pinfunction "P_3") (pintype "passive"))
      (node (ref "SW1") (pin "4") (pinfunction "P1_4") (pintype "passive"))
      (node (ref "SW2") (pin "3") (pinfunction "P_3") (pintype "passive"))
      (node (ref "SW2") (pin "4") (pinfunction "P1_4") (pintype "passive"))
      (node (ref "SW3") (pin "3") (pinfunction "P_3") (pintype "passive"))
      (node (ref "SW3") (pin "4") (pinfunction "P1_4") (pintype "passive"))
      (node (ref "SW4") (pin "3") (pinfunction "P_3") (pintype "passive"))
      (node (ref "SW4") (pin "4") (pinfunction "P1_4") (pintype "passive"))
      (node (ref "SW5") (pin "3") (pinfunction "P_3") (pintype "passive"))
      (node (ref "SW5") (pin "4") (pinfunction "P1_4") (pintype "passive"))
      (node (ref "TRA") (pin "P$1") (pinfunction "5_P$1") (pintype "passive"))
      (node (ref "TRA") (pin "P$2") (pinfunction "4_P$2") (pintype "passive"))
      (node (ref "TRF") (pin "P$1") (pinfunction "5_P$1") (pintype "passive"))
      (node (ref "U3") (pin "2") (pinfunction "GND_2") (pintype "power_in"))
      (node (ref "USB") (pin "5") (pinfunction "5_5") (pintype "passive"))
      (node (ref "X3") (pin "4") (pinfunction "4_4") (pintype "passive"))
      (node (ref "X5") (pin "GND") (pinfunction "GND_GND") (pintype "bidirectional"))
    )
    (net (code "50") (name "Net-(BUS-Pad1)") (class "Default")
      (node (ref "BUS") (pin "1") (pinfunction "1_1") (pintype "passive"))
      (node (ref "R53") (pin "1") (pinfunction "1_1") (pintype "passive"))
    )
    (net (code "51") (name "Net-(C10-Pad1)") (class "Default")
      (node (ref "C10") (pin "1") (pinfunction "1_1") (pintype "passive"))
      (node (ref "R14") (pin "1") (pinfunction "1_1") (pintype "passive"))
      (node (ref "R15") (pin "1") (pinfunction "1_1") (pintype "passive"))
      (node (ref "R16") (pin "2") (pinfunction "2_2") (pintype "passive"))
    )
    (net (code "52") (name "Net-(C13-Pad1)") (class "Default")
      (node (ref "C13") (pin "1") (pinfunction "1_1") (pintype "passive"))
      (node (ref "R17") (pin "2") (pinfunction "2_2") (pintype "passive"))
      (node (ref "R18") (pin "1") (pinfunction "1_1") (pintype "passive"))
      (node (ref "R19") (pin "2") (pinfunction "2_2") (pintype "passive"))
    )
    (net (code "53") (name "Net-(C14-Pad1)") (class "Default")
      (node (ref "C14") (pin "1") (pinfunction "1_1") (pintype "passive"))
      (node (ref "R20") (pin "1") (pinfunction "1_1") (pintype "passive"))
      (node (ref "R21") (pin "2") (pinfunction "2_2") (pintype "passive"))
      (node (ref "R22") (pin "2") (pinfunction "2_2") (pintype "passive"))
    )
    (net (code "54") (name "Net-(C18-Pad1)") (class "Default")
      (node (ref "C18") (pin "1") (pinfunction "1_1") (pintype "passive"))
      (node (ref "R25") (pin "1") (pinfunction "1_1") (pintype "passive"))
      (node (ref "R26") (pin "2") (pinfunction "2_2") (pintype "passive"))
      (node (ref "R28") (pin "1") (pinfunction "1_1") (pintype "passive"))
    )
    (net (code "55") (name "Net-(CV_A-3)") (class "Default")
      (node (ref "CV_A") (pin "P$3") (pinfunction "3_P$3") (pintype "passive"))
      (node (ref "R8") (pin "1") (pinfunction "1_1") (pintype "passive"))
    )
    (net (code "56") (name "Net-(CV_B-3)") (class "Default")
      (node (ref "CV_B") (pin "P$3") (pinfunction "3_P$3") (pintype "passive"))
      (node (ref "R31") (pin "1") (pinfunction "1_1") (pintype "passive"))
    )
    (net (code "57") (name "Net-(CV_F-3)") (class "Default")
      (node (ref "CV_F") (pin "P$3") (pinfunction "3_P$3") (pintype "passive"))
      (node (ref "R30") (pin "1") (pinfunction "1_1") (pintype "passive"))
    )
    (net (code "58") (name "Net-(CV_G-3)") (class "Default")
      (node (ref "CV_G") (pin "P$3") (pinfunction "3_P$3") (pintype "passive"))
      (node (ref "R33") (pin "1") (pinfunction "1_1") (pintype "passive"))
    )
    (net (code "59") (name "Net-(D1-C1A2)") (class "Default")
      (node (ref "D1") (pin "3") (pinfunction "C1A2_3") (pintype "passive"))
      (node (ref "R39") (pin "2") (pinfunction "2_2") (pintype "passive"))
      (node (ref "R40") (pin "1") (pinfunction "1_1") (pintype "passive"))
    )
    (net (code "60") (name "Net-(D2-C1A2)") (class "Default")
      (node (ref "D2") (pin "3") (pinfunction "C1A2_3") (pintype "passive"))
      (node (ref "R41") (pin "2") (pinfunction "2_2") (pintype "passive"))
      (node (ref "R42") (pin "1") (pinfunction "1_1") (pintype "passive"))
    )
    (net (code "61") (name "Net-(IC2A-+IN)") (class "Default")
      (node (ref "IC2") (pin "3") (pinfunction "+IN_3") (pintype "input"))
      (node (ref "R3") (pin "2") (pinfunction "2_2") (pintype "passive"))
      (node (ref "R4") (pin "1") (pinfunction "1_1") (pintype "passive"))
    )
    (net (code "62") (name "Net-(IC2A--IN)") (class "Default")
      (node (ref "IC2") (pin "2") (pinfunction "-IN_2") (pintype "input"))
      (node (ref "R1") (pin "2") (pinfunction "2_2") (pintype "passive"))
      (node (ref "R2") (pin "1") (pinfunction "1_1") (pintype "passive"))
    )
    (net (code "63") (name "Net-(IC2A-OUT)") (class "Default")
      (node (ref "IC2") (pin "1") (pinfunction "OUT_1") (pintype "output"))
      (node (ref "R1") (pin "1") (pinfunction "1_1") (pintype "passive"))
      (node (ref "R7") (pin "2") (pinfunction "2_2") (pintype "passive"))
    )
    (net (code "64") (name "Net-(IC2B-+IN)") (class "Default")
      (node (ref "IC2") (pin "5") (pinfunction "+IN_5") (pintype "input"))
      (node (ref "R5") (pin "2") (pinfunction "2_2") (pintype "passive"))
      (node (ref "R6") (pin "1") (pinfunction "1_1") (pintype "passive"))
    )
    (net (code "65") (name "Net-(IC2B--IN)") (class "Default")
      (node (ref "IC2") (pin "6") (pinfunction "-IN_6") (pintype "input"))
      (node (ref "R11") (pin "2") (pinfunction "2_2") (pintype "passive"))
      (node (ref "R12") (pin "1") (pinfunction "1_1") (pintype "passive"))
    )
    (net (code "66") (name "Net-(IC2B-OUT)") (class "Default")
      (node (ref "IC2") (pin "7") (pinfunction "OUT_7") (pintype "output"))
      (node (ref "R10") (pin "2") (pinfunction "2_2") (pintype "passive"))
      (node (ref "R11") (pin "1") (pinfunction "1_1") (pintype "passive"))
    )
    (net (code "67") (name "Net-(IC3A-+IN)") (class "Default")
      (node (ref "C21") (pin "1") (pinfunction "1_1") (pintype "passive"))
      (node (ref "IC3") (pin "3") (pinfunction "+IN_3") (pintype "input"))
      (node (ref "R18") (pin "2") (pinfunction "2_2") (pintype "passive"))
    )
    (net (code "68") (name "Net-(IC3A--IN)") (class "Default")
      (node (ref "C11") (pin "1") (pinfunction "1_1") (pintype "passive"))
      (node (ref "IC3") (pin "2") (pinfunction "-IN_2") (pintype "input"))
      (node (ref "R15") (pin "2") (pinfunction "2_2") (pintype "passive"))
    )
    (net (code "69") (name "Net-(IC3A-OUT)") (class "Default")
      (node (ref "C11") (pin "2") (pinfunction "2_2") (pintype "passive"))
      (node (ref "IC3") (pin "1") (pinfunction "OUT_1") (pintype "output"))
      (node (ref "R13") (pin "1") (pinfunction "1_1") (pintype "passive"))
      (node (ref "R14") (pin "2") (pinfunction "2_2") (pintype "passive"))
    )
    (net (code "70") (name "Net-(IC3B-+IN)") (class "Default")
      (node (ref "C22") (pin "1") (pinfunction "1_1") (pintype "passive"))
      (node (ref "IC3") (pin "5") (pinfunction "+IN_5") (pintype "input"))
      (node (ref "R20") (pin "2") (pinfunction "2_2") (pintype "passive"))
    )
    (net (code "71") (name "Net-(IC3B--IN)") (class "Default")
      (node (ref "C16") (pin "1") (pinfunction "1_1") (pintype "passive"))
      (node (ref "IC3") (pin "6") (pinfunction "-IN_6") (pintype "input"))
      (node (ref "R25") (pin "2") (pinfunction "2_2") (pintype "passive"))
    )
    (net (code "72") (name "Net-(IC3B-OUT)") (class "Default")
      (node (ref "C16") (pin "2") (pinfunction "2_2") (pintype "passive"))
      (node (ref "IC3") (pin "7") (pinfunction "OUT_7") (pintype "output"))
      (node (ref "R27") (pin "1") (pinfunction "1_1") (pintype "passive"))
      (node (ref "R28") (pin "2") (pinfunction "2_2") (pintype "passive"))
    )
    (net (code "73") (name "Net-(IC4A--IN)") (class "Default")
      (node (ref "IC4") (pin "2") (pinfunction "-IN_2") (pintype "input"))
      (node (ref "R24") (pin "1") (pinfunction "1_1") (pintype "passive"))
      (node (ref "R31") (pin "2") (pinfunction "2_2") (pintype "passive"))
      (node (ref "R32") (pin "2") (pinfunction "2_2") (pintype "passive"))
    )
    (net (code "74") (name "Net-(IC4A-OUT)") (class "Default")
      (node (ref "IC4") (pin "1") (pinfunction "OUT_1") (pintype "output"))
      (node (ref "R24") (pin "2") (pinfunction "2_2") (pintype "passive"))
      (node (ref "R42") (pin "2") (pinfunction "2_2") (pintype "passive"))
    )
    (net (code "75") (name "Net-(IC4B--IN)") (class "Default")
      (node (ref "C24") (pin "1") (pinfunction "1_1") (pintype "passive"))
      (node (ref "IC4") (pin "6") (pinfunction "-IN_6") (pintype "input"))
      (node (ref "R36") (pin "2") (pinfunction "2_2") (pintype "passive"))
      (node (ref "R37") (pin "2") (pinfunction "2_2") (pintype "passive"))
    )
    (net (code "76") (name "Net-(IC4B-OUT)") (class "Default")
      (node (ref "C24") (pin "2") (pinfunction "2_2") (pintype "passive"))
      (node (ref "IC4") (pin "7") (pinfunction "OUT_7") (pintype "output"))
      (node (ref "R33") (pin "2") (pinfunction "2_2") (pintype "passive"))
      (node (ref "R36") (pin "1") (pinfunction "1_1") (pintype "passive"))
    )
    (net (code "77") (name "Net-(IC4C--IN)") (class "Default")
      (node (ref "C23") (pin "1") (pinfunction "1_1") (pintype "passive"))
      (node (ref "IC4") (pin "9") (pinfunction "-IN_9") (pintype "input"))
      (node (ref "R34") (pin "2") (pinfunction "2_2") (pintype "passive"))
      (node (ref "R35") (pin "2") (pinfunction "2_2") (pintype "passive"))
    )
    (net (code "78") (name "Net-(IC4C-OUT)") (class "Default")
      (node (ref "C23") (pin "2") (pinfunction "2_2") (pintype "passive"))
      (node (ref "IC4") (pin "8") (pinfunction "OUT_8") (pintype "output"))
      (node (ref "R30") (pin "2") (pinfunction "2_2") (pintype "passive"))
      (node (ref "R34") (pin "1") (pinfunction "1_1") (pintype "passive"))
    )
    (net (code "79") (name "Net-(IC4D--IN)") (class "Default")
      (node (ref "IC4") (pin "13") (pinfunction "-IN_13") (pintype "input"))
      (node (ref "R23") (pin "1") (pinfunction "1_1") (pintype "passive"))
      (node (ref "R8") (pin "2") (pinfunction "2_2") (pintype "passive"))
      (node (ref "R9") (pin "2") (pinfunction "2_2") (pintype "passive"))
    )
    (net (code "80") (name "Net-(IC4D-OUT)") (class "Default")
      (node (ref "IC4") (pin "14") (pinfunction "OUT_14") (pintype "output"))
      (node (ref "R23") (pin "2") (pinfunction "2_2") (pintype "passive"))
      (node (ref "R40") (pin "2") (pinfunction "2_2") (pintype "passive"))
    )
    (net (code "81") (name "Net-(JP13-Pad2)") (class "Default")
      (node (ref "JP13") (pin "2") (pinfunction "2_2") (pintype "passive"))
      (node (ref "X5") (pin "VBUS") (pinfunction "VBUS_VBUS") (pintype "bidirectional"))
    )
    (net (code "82") (name "Net-(LED1-CBLUE)") (class "Default")
      (node (ref "LED1") (pin "P4") (pinfunction "CBLUE_P4") (pintype "passive"))
      (node (ref "R44") (pin "1") (pinfunction "1_1") (pintype "passive"))
    )
    (net (code "83") (name "Net-(LED1-CGREEN)") (class "Default")
      (node (ref "LED1") (pin "P2") (pinfunction "CGREEN_P2") (pintype "passive"))
      (node (ref "R45") (pin "1") (pinfunction "1_1") (pintype "passive"))
    )
    (net (code "84") (name "Net-(LED1-CRED)") (class "Default")
      (node (ref "LED1") (pin "P1") (pinfunction "CRED_P1") (pintype "passive"))
      (node (ref "R43") (pin "1") (pinfunction "1_1") (pintype "passive"))
    )
    (net (code "85") (name "Net-(POT_A-Pad2)") (class "Default")
      (node (ref "POT_A") (pin "2") (pinfunction "2_2") (pintype "bidirectional"))
      (node (ref "R9") (pin "1") (pinfunction "1_1") (pintype "passive"))
    )
    (net (code "86") (name "Net-(POT_B-Pad2)") (class "Default")
      (node (ref "POT_B") (pin "2") (pinfunction "2_2") (pintype "bidirectional"))
      (node (ref "R32") (pin "1") (pinfunction "1_1") (pintype "passive"))
    )
    (net (code "87") (name "Net-(Q1-D)") (class "Default")
      (node (ref "JP8") (pin "10") (pinfunction "10_10") (pintype "passive"))
      (node (ref "JP8") (pin "9") (pinfunction "9_9") (pintype "passive"))
      (node (ref "Q1") (pin "3") (pinfunction "D_3") (pintype "passive"))
    )
    (net (code "88") (name "Net-(Q2-D)") (class "Default")
      (node (ref "JP8") (pin "1") (pinfunction "1_1") (pintype "passive"))
      (node (ref "JP8") (pin "2") (pinfunction "2_2") (pintype "passive"))
      (node (ref "Q2") (pin "3") (pinfunction "D_3") (pintype "passive"))
    )
    (net (code "89") (name "Net-(Q3-B)") (class "Default")
      (node (ref "Q3") (pin "1") (pinfunction "B_1") (pintype "passive"))
      (node (ref "R49") (pin "2") (pinfunction "2_2") (pintype "passive"))
      (node (ref "R50") (pin "2") (pinfunction "2_2") (pintype "passive"))
    )
    (net (code "90") (name "Net-(Q903-B)") (class "Default")
      (node (ref "Q903") (pin "1") (pinfunction "B_1") (pintype "passive"))
      (node (ref "R38") (pin "1") (pinfunction "1_1") (pintype "passive"))
    )
    (net (code "91") (name "Net-(Q903-C)") (class "Default")
      (node (ref "Q903") (pin "3") (pinfunction "C_3") (pintype "passive"))
      (node (ref "R902") (pin "2") (pinfunction "2_2") (pintype "passive"))
      (node (ref "R903") (pin "1") (pinfunction "1_1") (pintype "passive"))
    )
    (net (code "92") (name "Net-(TRA-3)") (class "Default")
      (node (ref "R50") (pin "1") (pinfunction "1_1") (pintype "passive"))
      (node (ref "TRA") (pin "P$3") (pinfunction "3_P$3") (pintype "passive"))
    )
    (net (code "93") (name "unconnected-(OUT_L-4-PadP$2)") (class "Default")
      (node (ref "OUT_L") (pin "P$2") (pinfunction "4_P$2") (pintype "passive"))
    )
    (net (code "94") (name "unconnected-(OUT_R-4-PadP$2)") (class "Default")
      (node (ref "OUT_R") (pin "P$2") (pinfunction "4_P$2") (pintype "passive"))
    )
    (net (code "95") (name "unconnected-(TRF-4-PadP$2)") (class "Default")
      (node (ref "TRF") (pin "P$2") (pinfunction "4_P$2") (pintype "passive"))
    )
    (net (code "96") (name "unconnected-(X3-S1-PadM1)") (class "Default")
      (node (ref "X3") (pin "M1") (pinfunction "S1_M1") (pintype "passive"))
    )
    (net (code "97") (name "unconnected-(X3-S2-PadM2)") (class "Default")
      (node (ref "X3") (pin "M2") (pinfunction "S2_M2") (pintype "passive"))
    )
  )
)
